# SCH_StairLights_2023-11-12.net
KiCad netlist of a schematic drawn in EasyEDA
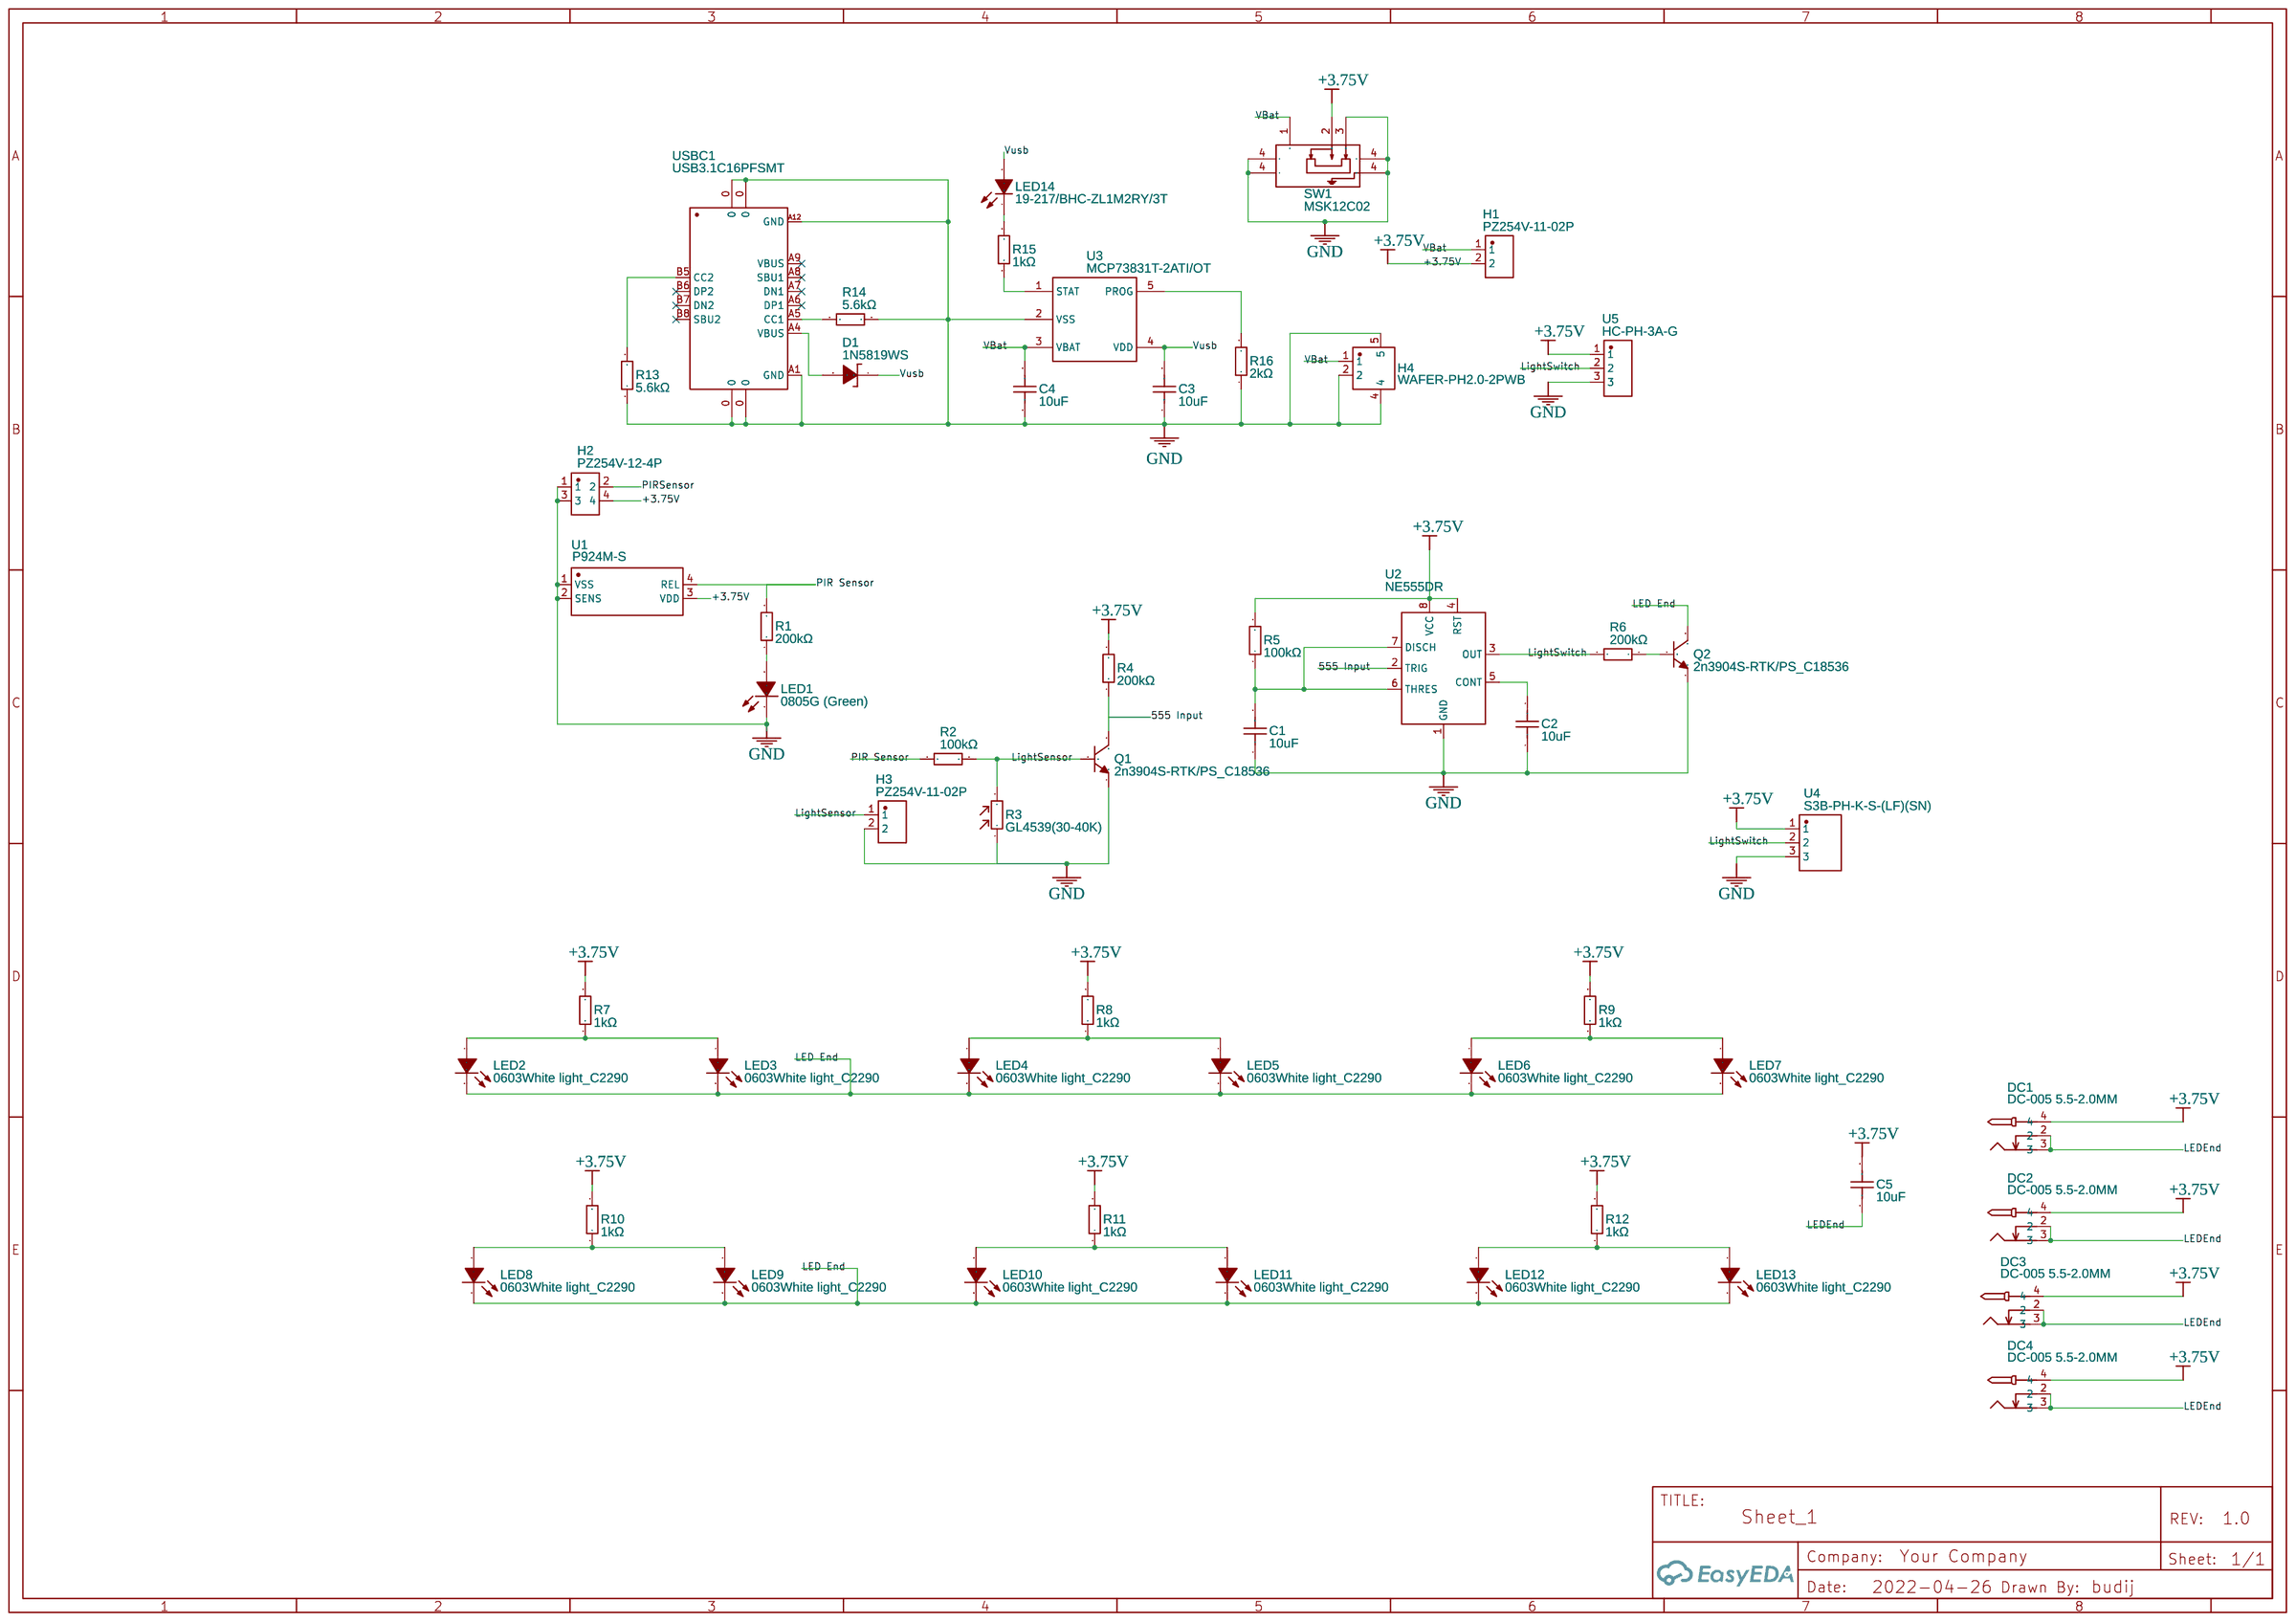
[diagram p0: schematic sheet]

(export (version "E")
  (design (tool "Eeschema 10.0.6"))
  (components
    (comp (ref "C1")
      (value "10uF")
      (fields
        (field (name "Manufacturer Part") "CL10A106KP8NNNC")
        (field (name "Manufacturer") "SAMSUNG(三星)")
      )
      (libsource (lib "") (part "CL10A106KP8NNNC"))
    )
    (comp (ref "C2")
      (value "10uF")
      (fields
        (field (name "Manufacturer Part") "CL10A106KP8NNNC")
        (field (name "Manufacturer") "SAMSUNG(三星)")
      )
      (libsource (lib "") (part "CL10A106KP8NNNC"))
    )
    (comp (ref "C3")
      (value "10uF")
      (fields
        (field (name "Manufacturer Part") "CL10A106KP8NNNC")
        (field (name "Manufacturer") "SAMSUNG(三星)")
      )
      (libsource (lib "") (part "CL10A106KP8NNNC"))
    )
    (comp (ref "C4")
      (value "10uF")
      (fields
        (field (name "Manufacturer Part") "CL10A106KP8NNNC")
        (field (name "Manufacturer") "SAMSUNG(三星)")
      )
      (libsource (lib "") (part "CL10A106KP8NNNC"))
    )
    (comp (ref "C5")
      (value "10uF")
      (fields
        (field (name "Manufacturer Part") "CL10A106KP8NNNC")
        (field (name "Manufacturer") "SAMSUNG(三星)")
      )
      (libsource (lib "") (part "CL10A106KP8NNNC"))
    )
    (comp (ref "D1")
      (value "1N5819WS")
      (fields (field (name "Manufacturer") "Hottech(合科泰)"))
      (libsource (lib "") (part "1N5819WS"))
    )
    (comp (ref "DC1")
      (value "DC-005 5.5-2.0MM")
      (fields (field (name "Manufacturer Part") "DC-005 2.0") (field (name "Manufacturer") "BOOMELE(博穆精密)"))
      (libsource (lib "") (part "DC-005 5.5-2.0MM"))
    )
    (comp (ref "DC2")
      (value "DC-005 5.5-2.0MM")
      (fields (field (name "Manufacturer Part") "DC-005 2.0") (field (name "Manufacturer") "BOOMELE(博穆精密)"))
      (libsource (lib "") (part "DC-005 5.5-2.0MM"))
    )
    (comp (ref "DC3")
      (value "DC-005 5.5-2.0MM")
      (fields (field (name "Manufacturer Part") "DC-005 2.0") (field (name "Manufacturer") "BOOMELE(博穆精密)"))
      (libsource (lib "") (part "DC-005 5.5-2.0MM"))
    )
    (comp (ref "DC4")
      (value "DC-005 5.5-2.0MM")
      (fields (field (name "Manufacturer Part") "DC-005 2.0") (field (name "Manufacturer") "BOOMELE(博穆精密)"))
      (libsource (lib "") (part "DC-005 5.5-2.0MM"))
    )
    (comp (ref "H1")
      (value "PZ254V-11-02P")
      (fields (field (name "Manufacturer") "XFCN"))
      (libsource (lib "") (part "PZ254V-11-02P"))
    )
    (comp (ref "H2")
      (value "PZ254V-12-4P")
      (fields (field (name "Manufacturer") "XFCN(兴飞)"))
      (libsource (lib "") (part "PZ254V-12-4P"))
    )
    (comp (ref "H3")
      (value "PZ254V-11-02P")
      (fields (field (name "Manufacturer") "XFCN"))
      (libsource (lib "") (part "PZ254V-11-02P"))
    )
    (comp (ref "H4")
      (value "WAFER-PH2.0-2PWB")
      (fields (field (name "Manufacturer") "XUNPU(讯普)"))
      (libsource (lib "") (part "WAFER-PH2.0-2PWB"))
    )
    (comp (ref "LED1")
      (value "0805G (Green)")
      (fields (field (name "Manufacturer") "KENTO"))
      (libsource (lib "") (part "0805G (Green)"))
    )
    (comp (ref "LED2")
      (value "0603White light_C2290")
      (fields (field (name "Manufacturer Part") "KT-0603白灯"))
      (libsource (lib "") (part "0603White light_C2290"))
    )
    (comp (ref "LED3")
      (value "0603White light_C2290")
      (fields (field (name "Manufacturer Part") "KT-0603白灯"))
      (libsource (lib "") (part "0603White light_C2290"))
    )
    (comp (ref "LED4")
      (value "0603White light_C2290")
      (fields (field (name "Manufacturer Part") "KT-0603白灯"))
      (libsource (lib "") (part "0603White light_C2290"))
    )
    (comp (ref "LED5")
      (value "0603White light_C2290")
      (fields (field (name "Manufacturer Part") "KT-0603白灯"))
      (libsource (lib "") (part "0603White light_C2290"))
    )
    (comp (ref "LED6")
      (value "0603White light_C2290")
      (fields (field (name "Manufacturer Part") "KT-0603白灯"))
      (libsource (lib "") (part "0603White light_C2290"))
    )
    (comp (ref "LED7")
      (value "0603White light_C2290")
      (fields (field (name "Manufacturer Part") "KT-0603白灯"))
      (libsource (lib "") (part "0603White light_C2290"))
    )
    (comp (ref "LED8")
      (value "0603White light_C2290")
      (fields (field (name "Manufacturer Part") "KT-0603白灯"))
      (libsource (lib "") (part "0603White light_C2290"))
    )
    (comp (ref "LED9")
      (value "0603White light_C2290")
      (fields (field (name "Manufacturer Part") "KT-0603白灯"))
      (libsource (lib "") (part "0603White light_C2290"))
    )
    (comp (ref "LED10")
      (value "0603White light_C2290")
      (fields (field (name "Manufacturer Part") "KT-0603白灯"))
      (libsource (lib "") (part "0603White light_C2290"))
    )
    (comp (ref "LED11")
      (value "0603White light_C2290")
      (fields (field (name "Manufacturer Part") "KT-0603白灯"))
      (libsource (lib "") (part "0603White light_C2290"))
    )
    (comp (ref "LED12")
      (value "0603White light_C2290")
      (fields (field (name "Manufacturer Part") "KT-0603白灯"))
      (libsource (lib "") (part "0603White light_C2290"))
    )
    (comp (ref "LED13")
      (value "0603White light_C2290")
      (fields (field (name "Manufacturer Part") "KT-0603白灯"))
      (libsource (lib "") (part "0603White light_C2290"))
    )
    (comp (ref "LED14")
      (value "19-217/BHC-ZL1M2RY/3T")
      (fields (field (name "Manufacturer") "EVERLIGHT(亿光)"))
      (libsource (lib "") (part "19-217/BHC-ZL1M2RY/3T"))
    )
    (comp (ref "Q1")
      (value "2n3904S-RTK/PS_C18536")
      (fields (field (name "Manufacturer Part") "2n3904S-RTK/PS") (field (name "Manufacturer") "KEC"))
      (libsource (lib "") (part "2n3904S-RTK/PS_C18536"))
    )
    (comp (ref "Q2")
      (value "2n3904S-RTK/PS_C18536")
      (fields (field (name "Manufacturer Part") "2n3904S-RTK/PS") (field (name "Manufacturer") "KEC"))
      (libsource (lib "") (part "2n3904S-RTK/PS_C18536"))
    )
    (comp (ref "R1")
      (value "200kΩ")
      (fields
        (field (name "Manufacturer Part") "0603WAF2003T5E")
        (field (name "Manufacturer") "UNI-ROYAL(厚声)")
      )
      (libsource (lib "") (part "0603WAF2003T5E"))
    )
    (comp (ref "R2")
      (value "100kΩ")
      (fields
        (field (name "Manufacturer Part") "0603WAF1003T5E")
        (field (name "Manufacturer") "UNI-ROYAL(厚声)")
      )
      (libsource (lib "") (part "0603WAF1003T5E"))
    )
    (comp (ref "R3")
      (value "GL4539(30-40K)")
      (fields (field (name "Manufacturer") "ReliaPro"))
      (libsource (lib "") (part "GL4539(30-40K)"))
    )
    (comp (ref "R4")
      (value "200kΩ")
      (fields
        (field (name "Manufacturer Part") "0603WAF2003T5E")
        (field (name "Manufacturer") "UNI-ROYAL(厚声)")
      )
      (libsource (lib "") (part "0603WAF2003T5E"))
    )
    (comp (ref "R5")
      (value "100kΩ")
      (fields
        (field (name "Manufacturer Part") "0603WAF1003T5E")
        (field (name "Manufacturer") "UNI-ROYAL(厚声)")
      )
      (libsource (lib "") (part "0603WAF1003T5E_1"))
    )
    (comp (ref "R6")
      (value "200kΩ")
      (fields
        (field (name "Manufacturer Part") "0603WAF2003T5E")
        (field (name "Manufacturer") "UNI-ROYAL(厚声)")
      )
      (libsource (lib "") (part "0603WAF2003T5E_1"))
    )
    (comp (ref "R7")
      (value "1kΩ")
      (fields
        (field (name "Manufacturer Part") "0603WAF1001T5E")
        (field (name "Manufacturer") "UNI-ROYAL(厚声)")
      )
      (libsource (lib "") (part "0603WAF1001T5E"))
    )
    (comp (ref "R8")
      (value "1kΩ")
      (fields
        (field (name "Manufacturer Part") "0603WAF1001T5E")
        (field (name "Manufacturer") "UNI-ROYAL(厚声)")
      )
      (libsource (lib "") (part "0603WAF1001T5E"))
    )
    (comp (ref "R9")
      (value "1kΩ")
      (fields
        (field (name "Manufacturer Part") "0603WAF1001T5E")
        (field (name "Manufacturer") "UNI-ROYAL(厚声)")
      )
      (libsource (lib "") (part "0603WAF1001T5E"))
    )
    (comp (ref "R10")
      (value "1kΩ")
      (fields
        (field (name "Manufacturer Part") "0603WAF1001T5E")
        (field (name "Manufacturer") "UNI-ROYAL(厚声)")
      )
      (libsource (lib "") (part "0603WAF1001T5E"))
    )
    (comp (ref "R11")
      (value "1kΩ")
      (fields
        (field (name "Manufacturer Part") "0603WAF1001T5E")
        (field (name "Manufacturer") "UNI-ROYAL(厚声)")
      )
      (libsource (lib "") (part "0603WAF1001T5E"))
    )
    (comp (ref "R12")
      (value "1kΩ")
      (fields
        (field (name "Manufacturer Part") "0603WAF1001T5E")
        (field (name "Manufacturer") "UNI-ROYAL(厚声)")
      )
      (libsource (lib "") (part "0603WAF1001T5E"))
    )
    (comp (ref "R13")
      (value "5.6kΩ")
      (fields
        (field (name "Manufacturer Part") "0603WAF5601T5E")
        (field (name "Manufacturer") "UNI-ROYAL(厚声)")
      )
      (libsource (lib "") (part "0603WAF5601T5E_1"))
    )
    (comp (ref "R14")
      (value "5.6kΩ")
      (fields
        (field (name "Manufacturer Part") "0603WAF5601T5E")
        (field (name "Manufacturer") "UNI-ROYAL(厚声)")
      )
      (libsource (lib "") (part "0603WAF5601T5E"))
    )
    (comp (ref "R15")
      (value "1kΩ")
      (fields
        (field (name "Manufacturer Part") "0603WAF1001T5E")
        (field (name "Manufacturer") "UNI-ROYAL(厚声)")
      )
      (libsource (lib "") (part "0603WAF1001T5E"))
    )
    (comp (ref "R16")
      (value "2kΩ")
      (fields
        (field (name "Manufacturer Part") "0603WAF2001T5E")
        (field (name "Manufacturer") "UNI-ROYAL(厚声)")
      )
      (libsource (lib "") (part "0603WAF2001T5E"))
    )
    (comp (ref "SW1")
      (value "MSK12C02")
      (fields (field (name "Manufacturer") "SHOU HAN(首韩)"))
      (libsource (lib "") (part "MSK12C02"))
    )
    (comp (ref "U1")
      (value "P924M-S")
      (fields (field (name "Manufacturer") "Nicera"))
      (libsource (lib "") (part "P924M-S"))
    )
    (comp (ref "U2")
      (value "NE555DR")
      (fields (field (name "Manufacturer") "TI"))
      (libsource (lib "") (part "NE555DR"))
    )
    (comp (ref "U3")
      (value "MCP73831T-2ATI/OT")
      (fields (field (name "Manufacturer") "MICROCHIP"))
      (libsource (lib "") (part "MCP73831T-2ATI/OT"))
    )
    (comp (ref "U4")
      (value "S3B-PH-K-S-(LF)(SN)")
      (fields (field (name "Manufacturer Part") "S3B-PH-K-S(LF)(SN)") (field (name "Manufacturer") "JST"))
      (libsource (lib "") (part "S3B-PH-K-S-(LF)(SN)"))
    )
    (comp (ref "U5")
      (value "HC-PH-3A-G")
      (fields (field (name "Manufacturer") "HCTL(华灿天禄)"))
      (libsource (lib "") (part "HC-PH-3A-G"))
    )
    (comp (ref "USBC1")
      (value "USB3.1C16PFSMT")
      (fields (field (name "Manufacturer") "LCSC"))
      (libsource (lib "") (part "USB3.1C16PFSMT"))
    )
  )
  (nets
    (net (code "1") (name "+3.75V") (class "Default")
      (node (ref "C5") (pin "2") (pinfunction "2_2") (pintype "unspecified"))
      (node (ref "DC1") (pin "4") (pinfunction "4_4") (pintype "unspecified"))
      (node (ref "DC2") (pin "4") (pinfunction "4_4") (pintype "unspecified"))
      (node (ref "DC3") (pin "4") (pinfunction "4_4") (pintype "unspecified"))
      (node (ref "DC4") (pin "4") (pinfunction "4_4") (pintype "unspecified"))
      (node (ref "H1") (pin "2") (pinfunction "2_2") (pintype "unspecified"))
      (node (ref "H2") (pin "4") (pinfunction "4_4") (pintype "unspecified"))
      (node (ref "R10") (pin "2") (pinfunction "2_2") (pintype "input"))
      (node (ref "R11") (pin "2") (pinfunction "2_2") (pintype "input"))
      (node (ref "R12") (pin "2") (pinfunction "2_2") (pintype "input"))
      (node (ref "R4") (pin "2") (pinfunction "2_2") (pintype "input"))
      (node (ref "R5") (pin "2") (pinfunction "2_2") (pintype "input"))
      (node (ref "R7") (pin "2") (pinfunction "2_2") (pintype "input"))
      (node (ref "R8") (pin "2") (pinfunction "2_2") (pintype "input"))
      (node (ref "R9") (pin "2") (pinfunction "2_2") (pintype "input"))
      (node (ref "SW1") (pin "2") (pinfunction "2_2") (pintype "unspecified"))
      (node (ref "U1") (pin "3") (pinfunction "VDD_3") (pintype "unspecified"))
      (node (ref "U2") (pin "4") (pinfunction "RST_4") (pintype "unspecified"))
      (node (ref "U2") (pin "8") (pinfunction "VCC_8") (pintype "unspecified"))
      (node (ref "U4") (pin "1") (pinfunction "1_1") (pintype "unspecified"))
      (node (ref "U5") (pin "1") (pinfunction "1_1") (pintype "unspecified"))
    )
    (net (code "2") (name "/555 Input") (class "Default")
      (node (ref "Q1") (pin "3") (pinfunction "C_3") (pintype "input"))
      (node (ref "R4") (pin "1") (pinfunction "1_1") (pintype "input"))
      (node (ref "U2") (pin "2") (pinfunction "TRIG_2") (pintype "unspecified"))
    )
    (net (code "3") (name "/LED End") (class "Default")
      (node (ref "LED10") (pin "2") (pinfunction "K_2") (pintype "unspecified"))
      (node (ref "LED11") (pin "2") (pinfunction "K_2") (pintype "unspecified"))
      (node (ref "LED12") (pin "2") (pinfunction "K_2") (pintype "unspecified"))
      (node (ref "LED13") (pin "2") (pinfunction "K_2") (pintype "unspecified"))
      (node (ref "LED2") (pin "2") (pinfunction "K_2") (pintype "unspecified"))
      (node (ref "LED3") (pin "2") (pinfunction "K_2") (pintype "unspecified"))
      (node (ref "LED4") (pin "2") (pinfunction "K_2") (pintype "unspecified"))
      (node (ref "LED5") (pin "2") (pinfunction "K_2") (pintype "unspecified"))
      (node (ref "LED6") (pin "2") (pinfunction "K_2") (pintype "unspecified"))
      (node (ref "LED7") (pin "2") (pinfunction "K_2") (pintype "unspecified"))
      (node (ref "LED8") (pin "2") (pinfunction "K_2") (pintype "unspecified"))
      (node (ref "LED9") (pin "2") (pinfunction "K_2") (pintype "unspecified"))
      (node (ref "Q2") (pin "3") (pinfunction "C_3") (pintype "input"))
    )
    (net (code "4") (name "/LEDEnd") (class "Default")
      (node (ref "C5") (pin "1") (pinfunction "1_1") (pintype "unspecified"))
      (node (ref "DC1") (pin "2") (pinfunction "2_2") (pintype "unspecified"))
      (node (ref "DC1") (pin "3") (pinfunction "3_3") (pintype "unspecified"))
      (node (ref "DC2") (pin "2") (pinfunction "2_2") (pintype "unspecified"))
      (node (ref "DC2") (pin "3") (pinfunction "3_3") (pintype "unspecified"))
      (node (ref "DC3") (pin "2") (pinfunction "2_2") (pintype "unspecified"))
      (node (ref "DC3") (pin "3") (pinfunction "3_3") (pintype "unspecified"))
      (node (ref "DC4") (pin "2") (pinfunction "2_2") (pintype "unspecified"))
      (node (ref "DC4") (pin "3") (pinfunction "3_3") (pintype "unspecified"))
    )
    (net (code "5") (name "/LightSensor") (class "Default")
      (node (ref "H3") (pin "1") (pinfunction "1_1") (pintype "unspecified"))
      (node (ref "Q1") (pin "2") (pinfunction "B_2") (pintype "input"))
      (node (ref "R2") (pin "2") (pinfunction "2_2") (pintype "input"))
      (node (ref "R3") (pin "2") (pinfunction "2_2") (pintype "input"))
    )
    (net (code "6") (name "/LightSwitch") (class "Default")
      (node (ref "R6") (pin "2") (pinfunction "2_2") (pintype "input"))
      (node (ref "U2") (pin "3") (pinfunction "OUT_3") (pintype "unspecified"))
      (node (ref "U4") (pin "2") (pinfunction "2_2") (pintype "unspecified"))
      (node (ref "U5") (pin "2") (pinfunction "2_2") (pintype "unspecified"))
    )
    (net (code "7") (name "/PIR Sensor") (class "Default")
      (node (ref "R1") (pin "2") (pinfunction "2_2") (pintype "input"))
      (node (ref "R2") (pin "1") (pinfunction "1_1") (pintype "input"))
      (node (ref "U1") (pin "4") (pinfunction "REL_4") (pintype "unspecified"))
    )
    (net (code "8") (name "/PIRSensor") (class "Default")
      (node (ref "H2") (pin "2") (pinfunction "2_2") (pintype "unspecified"))
    )
    (net (code "9") (name "/VBat") (class "Default")
      (node (ref "C4") (pin "2") (pinfunction "2_2") (pintype "unspecified"))
      (node (ref "H1") (pin "1") (pinfunction "1_1") (pintype "unspecified"))
      (node (ref "H4") (pin "1") (pinfunction "1_1") (pintype "unspecified"))
      (node (ref "SW1") (pin "1") (pinfunction "1_1") (pintype "unspecified"))
      (node (ref "U3") (pin "3") (pinfunction "VBAT_3") (pintype "unspecified"))
    )
    (net (code "10") (name "/Vusb") (class "Default")
      (node (ref "C3") (pin "2") (pinfunction "2_2") (pintype "unspecified"))
      (node (ref "D1") (pin "1") (pinfunction "C_1") (pintype "unspecified"))
      (node (ref "LED14") (pin "2") (pinfunction "A_2") (pintype "input"))
      (node (ref "U3") (pin "4") (pinfunction "VDD_4") (pintype "unspecified"))
    )
    (net (code "11") (name "GND") (class "Default")
      (node (ref "C1") (pin "1") (pinfunction "1_1") (pintype "unspecified"))
      (node (ref "C2") (pin "1") (pinfunction "1_1") (pintype "unspecified"))
      (node (ref "C3") (pin "1") (pinfunction "1_1") (pintype "unspecified"))
      (node (ref "C4") (pin "1") (pinfunction "1_1") (pintype "unspecified"))
      (node (ref "H2") (pin "1") (pinfunction "1_1") (pintype "unspecified"))
      (node (ref "H2") (pin "3") (pinfunction "3_3") (pintype "unspecified"))
      (node (ref "H3") (pin "2") (pinfunction "2_2") (pintype "unspecified"))
      (node (ref "H4") (pin "2") (pinfunction "2_2") (pintype "unspecified"))
      (node (ref "H4") (pin "4") (pinfunction "4_4") (pintype "unspecified"))
      (node (ref "H4") (pin "5") (pinfunction "5_5") (pintype "unspecified"))
      (node (ref "LED1") (pin "1") (pinfunction "K_1") (pintype "unspecified"))
      (node (ref "Q1") (pin "1") (pinfunction "E_1") (pintype "input"))
      (node (ref "Q2") (pin "1") (pinfunction "E_1") (pintype "input"))
      (node (ref "R13") (pin "1") (pinfunction "1_1") (pintype "input"))
      (node (ref "R14") (pin "2") (pinfunction "2_2") (pintype "input"))
      (node (ref "R16") (pin "1") (pinfunction "1_1") (pintype "input"))
      (node (ref "R3") (pin "1") (pinfunction "1_1") (pintype "input"))
      (node (ref "SW1") (pin "3") (pinfunction "3_3") (pintype "unspecified"))
      (node (ref "SW1") (pin "4") (pinfunction "4_4") (pintype "unspecified"))
      (node (ref "U1") (pin "1") (pinfunction "VSS_1") (pintype "unspecified"))
      (node (ref "U1") (pin "2") (pinfunction "SENS_2") (pintype "unspecified"))
      (node (ref "U2") (pin "1") (pinfunction "GND_1") (pintype "unspecified"))
      (node (ref "U3") (pin "2") (pinfunction "VSS_2") (pintype "unspecified"))
      (node (ref "U4") (pin "3") (pinfunction "3_3") (pintype "unspecified"))
      (node (ref "U5") (pin "3") (pinfunction "3_3") (pintype "unspecified"))
      (node (ref "USBC1") (pin "0") (pinfunction "0_0") (pintype "unspecified"))
      (node (ref "USBC1") (pin "A1") (pinfunction "GND_A1") (pintype "unspecified"))
      (node (ref "USBC1") (pin "A12") (pinfunction "GND_A12") (pintype "unspecified"))
    )
    (net (code "12") (name "Net-(D1-A)") (class "Default")
      (node (ref "D1") (pin "2") (pinfunction "A_2") (pintype "unspecified"))
      (node (ref "USBC1") (pin "A4") (pinfunction "VBUS_A4") (pintype "unspecified"))
    )
    (net (code "13") (name "Net-(LED1-A)") (class "Default")
      (node (ref "LED1") (pin "2") (pinfunction "A_2") (pintype "unspecified"))
      (node (ref "R1") (pin "1") (pinfunction "1_1") (pintype "input"))
    )
    (net (code "14") (name "Net-(LED2-A)") (class "Default")
      (node (ref "LED2") (pin "1") (pinfunction "A_1") (pintype "unspecified"))
      (node (ref "LED3") (pin "1") (pinfunction "A_1") (pintype "unspecified"))
      (node (ref "R7") (pin "1") (pinfunction "1_1") (pintype "input"))
    )
    (net (code "15") (name "Net-(LED4-A)") (class "Default")
      (node (ref "LED4") (pin "1") (pinfunction "A_1") (pintype "unspecified"))
      (node (ref "LED5") (pin "1") (pinfunction "A_1") (pintype "unspecified"))
      (node (ref "R8") (pin "1") (pinfunction "1_1") (pintype "input"))
    )
    (net (code "16") (name "Net-(LED6-A)") (class "Default")
      (node (ref "LED6") (pin "1") (pinfunction "A_1") (pintype "unspecified"))
      (node (ref "LED7") (pin "1") (pinfunction "A_1") (pintype "unspecified"))
      (node (ref "R9") (pin "1") (pinfunction "1_1") (pintype "input"))
    )
    (net (code "17") (name "Net-(LED8-A)") (class "Default")
      (node (ref "LED8") (pin "1") (pinfunction "A_1") (pintype "unspecified"))
      (node (ref "LED9") (pin "1") (pinfunction "A_1") (pintype "unspecified"))
      (node (ref "R10") (pin "1") (pinfunction "1_1") (pintype "input"))
    )
    (net (code "18") (name "Net-(LED10-A)") (class "Default")
      (node (ref "LED10") (pin "1") (pinfunction "A_1") (pintype "unspecified"))
      (node (ref "LED11") (pin "1") (pinfunction "A_1") (pintype "unspecified"))
      (node (ref "R11") (pin "1") (pinfunction "1_1") (pintype "input"))
    )
    (net (code "19") (name "Net-(LED12-A)") (class "Default")
      (node (ref "LED12") (pin "1") (pinfunction "A_1") (pintype "unspecified"))
      (node (ref "LED13") (pin "1") (pinfunction "A_1") (pintype "unspecified"))
      (node (ref "R12") (pin "1") (pinfunction "1_1") (pintype "input"))
    )
    (net (code "20") (name "Net-(LED14-C)") (class "Default")
      (node (ref "LED14") (pin "1") (pinfunction "C_1") (pintype "input"))
      (node (ref "R15") (pin "2") (pinfunction "2_2") (pintype "input"))
    )
    (net (code "21") (name "Net-(Q2-B)") (class "Default")
      (node (ref "Q2") (pin "2") (pinfunction "B_2") (pintype "input"))
      (node (ref "R6") (pin "1") (pinfunction "1_1") (pintype "input"))
    )
    (net (code "22") (name "Net-(U2-CONT)") (class "Default")
      (node (ref "C2") (pin "2") (pinfunction "2_2") (pintype "unspecified"))
      (node (ref "U2") (pin "5") (pinfunction "CONT_5") (pintype "unspecified"))
    )
    (net (code "23") (name "Net-(U2-DISCH)") (class "Default")
      (node (ref "C1") (pin "2") (pinfunction "2_2") (pintype "unspecified"))
      (node (ref "R5") (pin "1") (pinfunction "1_1") (pintype "input"))
      (node (ref "U2") (pin "6") (pinfunction "THRES_6") (pintype "unspecified"))
      (node (ref "U2") (pin "7") (pinfunction "DISCH_7") (pintype "unspecified"))
    )
    (net (code "24") (name "Net-(U3-PROG)") (class "Default")
      (node (ref "R16") (pin "2") (pinfunction "2_2") (pintype "input"))
      (node (ref "U3") (pin "5") (pinfunction "PROG_5") (pintype "unspecified"))
    )
    (net (code "25") (name "Net-(U3-STAT)") (class "Default")
      (node (ref "R15") (pin "1") (pinfunction "1_1") (pintype "input"))
      (node (ref "U3") (pin "1") (pinfunction "STAT_1") (pintype "unspecified"))
    )
    (net (code "26") (name "Net-(USBC1-CC1)") (class "Default")
      (node (ref "R14") (pin "1") (pinfunction "1_1") (pintype "input"))
      (node (ref "USBC1") (pin "A5") (pinfunction "CC1_A5") (pintype "unspecified"))
    )
    (net (code "27") (name "Net-(USBC1-CC2)") (class "Default")
      (node (ref "R13") (pin "2") (pinfunction "2_2") (pintype "input"))
      (node (ref "USBC1") (pin "B5") (pinfunction "CC2_B5") (pintype "unspecified"))
    )
    (net (code "28") (name "unconnected-(USBC1-DN1-PadA7)") (class "Default")
      (node (ref "USBC1") (pin "A7") (pinfunction "DN1_A7") (pintype "unspecified+no_connect"))
    )
    (net (code "29") (name "unconnected-(USBC1-DN2-PadB7)") (class "Default")
      (node (ref "USBC1") (pin "B7") (pinfunction "DN2_B7") (pintype "unspecified+no_connect"))
    )
    (net (code "30") (name "unconnected-(USBC1-DP1-PadA6)") (class "Default")
      (node (ref "USBC1") (pin "A6") (pinfunction "DP1_A6") (pintype "unspecified+no_connect"))
    )
    (net (code "31") (name "unconnected-(USBC1-DP2-PadB6)") (class "Default")
      (node (ref "USBC1") (pin "B6") (pinfunction "DP2_B6") (pintype "unspecified+no_connect"))
    )
    (net (code "32") (name "unconnected-(USBC1-SBU1-PadA8)") (class "Default")
      (node (ref "USBC1") (pin "A8") (pinfunction "SBU1_A8") (pintype "unspecified+no_connect"))
    )
    (net (code "33") (name "unconnected-(USBC1-SBU2-PadB8)") (class "Default")
      (node (ref "USBC1") (pin "B8") (pinfunction "SBU2_B8") (pintype "unspecified+no_connect"))
    )
    (net (code "34") (name "unconnected-(USBC1-VBUS-PadA9)") (class "Default")
      (node (ref "USBC1") (pin "A9") (pinfunction "VBUS_A9") (pintype "unspecified+no_connect"))
    )
  )
)
